# KC_BaseBoard4CompareTest-V0_1_NT.net
KiCad netlist of a schematic drawn in Altium Designer
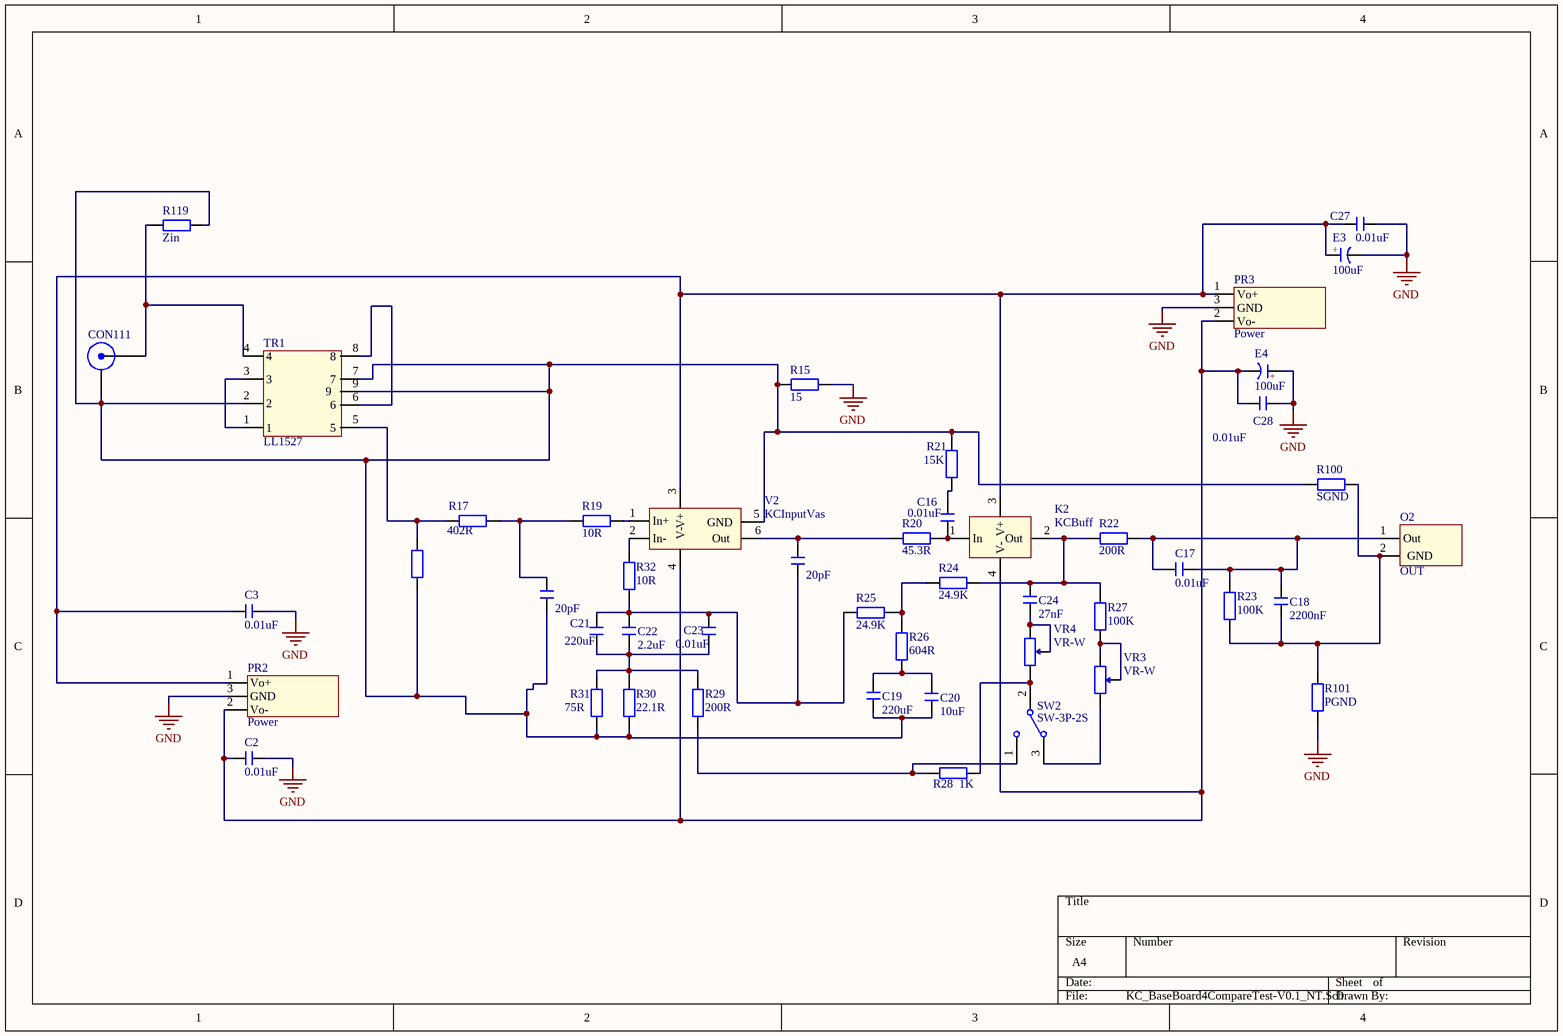
[diagram p0: KC_BaseBoard4CompareTest-V0.1_NT.SchDoc]

(export (version "E")
  (design (tool "Eeschema 10.0.6"))
  (components
    (comp (ref "C2")
      (value "0.01uF")
      (footprint "CBB 6.3*6.3*5")
      (description "CBB电容")
      (fields (field (name "版权归属") "源创客"))
      (libsource (lib "电阻-电容-电感") (part "C-CBB"))
    )
    (comp (ref "C3")
      (value "0.01uF")
      (footprint "CBB 6.3*6.3*5")
      (description "CBB电容")
      (fields (field (name "版权归属") "源创客"))
      (libsource (lib "电阻-电容-电感") (part "C-CBB"))
    )
    (comp (ref "C16")
      (value "0.01uF")
      (footprint "CBB 6.3*6.3*5")
      (description "CBB电容")
      (fields (field (name "版权归属") "源创客"))
      (libsource (lib "电阻-电容-电感") (part "C-CBB"))
    )
    (comp (ref "C17")
      (value "0.01uF")
      (footprint "CBB 6.3*6.3*5")
      (description "CBB电容")
      (fields (field (name "版权归属") "源创客"))
      (libsource (lib "电阻-电容-电感") (part "C-CBB"))
    )
    (comp (ref "C18")
      (value "2200nF")
      (footprint "CBB 6.3*6.3*5")
      (description "CBB电容")
      (fields (field (name "版权归属") "源创客"))
      (libsource (lib "电阻-电容-电感") (part "C-CBB"))
    )
    (comp (ref "C19")
      (value "220uF")
      (footprint "CBB 6.3*6.3*5")
      (description "CBB电容")
      (fields (field (name "版权归属") "源创客"))
      (libsource (lib "电阻-电容-电感") (part "C-CBB"))
    )
    (comp (ref "C20")
      (value "10uF")
      (footprint "CBB 6.3*6.3*5")
      (description "CBB电容")
      (fields (field (name "版权归属") "源创客"))
      (libsource (lib "电阻-电容-电感") (part "C-CBB"))
    )
    (comp (ref "C21")
      (value "220uF")
      (footprint "CBB 6.3*6.3*5")
      (description "CBB电容")
      (fields (field (name "版权归属") "源创客"))
      (libsource (lib "电阻-电容-电感") (part "C-CBB"))
    )
    (comp (ref "C22")
      (value "2.2uF")
      (footprint "CBB 6.3*6.3*5")
      (description "CBB电容")
      (fields (field (name "版权归属") "源创客"))
      (libsource (lib "电阻-电容-电感") (part "C-CBB"))
    )
    (comp (ref "C23")
      (value "0.01uF")
      (footprint "CBB 6.3*6.3*5")
      (description "CBB电容")
      (fields (field (name "版权归属") "源创客"))
      (libsource (lib "电阻-电容-电感") (part "C-CBB"))
    )
    (comp (ref "C24")
      (value "27nF")
      (footprint "CBB 6.3*6.3*5")
      (description "CBB电容")
      (fields (field (name "版权归属") "源创客"))
      (libsource (lib "电阻-电容-电感") (part "C-CBB"))
    )
    (comp (ref "C27")
      (value "0.01uF")
      (footprint "CBB 6.3*6.3*5")
      (description "CBB电容")
      (fields (field (name "版权归属") "源创客"))
      (libsource (lib "电阻-电容-电感") (part "C-CBB"))
    )
    (comp (ref "C28")
      (value "0.01uF")
      (footprint "CBB 6.3*6.3*5")
      (description "CBB电容")
      (fields (field (name "版权归属") "源创客"))
      (libsource (lib "电阻-电容-电感") (part "C-CBB"))
    )
    (comp (ref "C303")
      (value "20pF")
      (footprint "CBB 6.3*6.3*5")
      (description "CBB电容")
      (fields (field (name "版权归属") "源创客"))
      (libsource (lib "电阻-电容-电感") (part "C-CBB"))
    )
    (comp (ref "C403")
      (value "20pF")
      (footprint "CBB 6.3*6.3*5")
      (description "CBB电容")
      (fields (field (name "版权归属") "源创客"))
      (libsource (lib "电阻-电容-电感") (part "C-CBB"))
    )
    (comp (ref "CON111")
      (value "RCA")
      (footprint "SMB_V-RJ45")
      (description "RCA Connector")
      (fields (field (name "PUBLISHER") "Altium Limited"))
      (libsource (lib "Connectors") (part "RCA"))
    )
    (comp (ref "E3")
      (value "100uF")
      (footprint "CAP 5.0*6.5*12.5")
      (description "直插电解电容")
      (fields (field (name "版权归属") "源创客"))
      (libsource (lib "电阻-电容-电感") (part "C-CAP"))
    )
    (comp (ref "E4")
      (value "100uF")
      (footprint "CAP 5.0*6.5*12.5")
      (description "直插电解电容")
      (fields (field (name "版权归属") "源创客"))
      (libsource (lib "电阻-电容-电感") (part "C-CAP"))
    )
    (comp (ref "K2")
      (value "KCBuff")
      (footprint "KCBuff_M4")
      (description "King Cello Buffer Stage")
      (libsource (lib "KC_amp") (part "KCBuff"))
    )
    (comp (ref "O2")
      (value "OUT")
      (footprint "Signal_Terminal")
      (description "Signal Out")
      (libsource (lib "KC_amp") (part "Signal_Out"))
    )
    (comp (ref "PR2")
      (value "Power")
      (footprint "KC_MBPowerReg4Compare-1.5mm")
      (description "King Cello Compare Test Power")
      (libsource (lib "KC_amp") (part "MainBoardPowerRegulator4CompareTest"))
    )
    (comp (ref "PR3")
      (value "Power")
      (footprint "KC_MBPowerReg4Compare-1.5mm")
      (description "King Cello Compare Test Power")
      (libsource (lib "KC_amp") (part "MainBoardPowerRegulator4CompareTest"))
    )
    (comp (ref "R15")
      (value "15")
      (footprint "RS 1/4W")
      (description "直插色环电阻")
      (fields (field (name "版权归属") "源创客"))
      (libsource (lib "电阻-电容-电感") (part "R-CRR"))
    )
    (comp (ref "R17")
      (value "402R")
      (footprint "RS 1/4W")
      (description "直插色环电阻")
      (fields (field (name "版权归属") "源创客"))
      (libsource (lib "电阻-电容-电感") (part "R-CRR"))
    )
    (comp (ref "R19")
      (value "10R")
      (footprint "RS 1/4W")
      (description "直插色环电阻")
      (fields (field (name "版权归属") "源创客"))
      (libsource (lib "电阻-电容-电感") (part "R-CRR"))
    )
    (comp (ref "R20")
      (value "45.3R")
      (footprint "RS 1/4W")
      (description "直插色环电阻")
      (fields (field (name "版权归属") "源创客"))
      (libsource (lib "电阻-电容-电感") (part "R-CRR"))
    )
    (comp (ref "R21")
      (value "15K")
      (footprint "RS 1/4W")
      (description "直插色环电阻")
      (fields (field (name "版权归属") "源创客"))
      (libsource (lib "电阻-电容-电感") (part "R-CRR"))
    )
    (comp (ref "R22")
      (value "200R")
      (footprint "RS 1/4W")
      (description "直插色环电阻")
      (fields (field (name "版权归属") "源创客"))
      (libsource (lib "电阻-电容-电感") (part "R-CRR"))
    )
    (comp (ref "R23")
      (value "100K")
      (footprint "RS 1/4W")
      (description "直插色环电阻")
      (fields (field (name "版权归属") "源创客"))
      (libsource (lib "电阻-电容-电感") (part "R-CRR"))
    )
    (comp (ref "R24")
      (value "24.9K")
      (footprint "RS 1/4W")
      (description "直插色环电阻")
      (fields (field (name "版权归属") "源创客"))
      (libsource (lib "电阻-电容-电感") (part "R-CRR"))
    )
    (comp (ref "R25")
      (value "24.9K")
      (footprint "RS 1/4W")
      (description "直插色环电阻")
      (fields (field (name "版权归属") "源创客"))
      (libsource (lib "电阻-电容-电感") (part "R-CRR"))
    )
    (comp (ref "R26")
      (value "604R")
      (footprint "RS 1/4W")
      (description "直插色环电阻")
      (fields (field (name "版权归属") "源创客"))
      (libsource (lib "电阻-电容-电感") (part "R-CRR"))
    )
    (comp (ref "R27")
      (value "100K")
      (footprint "RS 1/4W")
      (description "直插色环电阻")
      (fields (field (name "版权归属") "源创客"))
      (libsource (lib "电阻-电容-电感") (part "R-CRR"))
    )
    (comp (ref "R28")
      (value "1K")
      (footprint "RS 1/4W")
      (description "直插色环电阻")
      (fields (field (name "版权归属") "源创客"))
      (libsource (lib "电阻-电容-电感") (part "R-CRR"))
    )
    (comp (ref "R29")
      (value "200R")
      (footprint "RS 1/4W")
      (description "直插色环电阻")
      (fields (field (name "版权归属") "源创客"))
      (libsource (lib "电阻-电容-电感") (part "R-CRR"))
    )
    (comp (ref "R30")
      (value "22.1R")
      (footprint "RS 1/4W")
      (description "直插色环电阻")
      (fields (field (name "版权归属") "源创客"))
      (libsource (lib "电阻-电容-电感") (part "R-CRR"))
    )
    (comp (ref "R31")
      (value "75R")
      (footprint "RS 1/4W")
      (description "直插色环电阻")
      (fields (field (name "版权归属") "源创客"))
      (libsource (lib "电阻-电容-电感") (part "R-CRR"))
    )
    (comp (ref "R32")
      (value "10R")
      (footprint "RS 1/4W")
      (description "直插色环电阻")
      (fields (field (name "版权归属") "源创客"))
      (libsource (lib "电阻-电容-电感") (part "R-CRR"))
    )
    (comp (ref "R100")
      (value "SGND")
      (footprint "RS 1/4W")
      (description "直插色环电阻")
      (fields (field (name "版权归属") "源创客"))
      (libsource (lib "电阻-电容-电感") (part "R-CRR"))
    )
    (comp (ref "R101")
      (value "PGND")
      (footprint "RS 1/4W")
      (description "直插色环电阻")
      (fields (field (name "版权归属") "源创客"))
      (libsource (lib "电阻-电容-电感") (part "R-CRR"))
    )
    (comp (ref "R119")
      (value "Zin")
      (footprint "RS 1/4W")
      (description "直插色环电阻")
      (fields (field (name "版权归属") "源创客"))
      (libsource (lib "电阻-电容-电感") (part "R-CRR"))
    )
    (comp (ref "R183")
      (value "47K")
      (footprint "RS 1/4W")
      (description "直插色环电阻")
      (fields (field (name "版权归属") "源创客"))
      (libsource (lib "电阻-电容-电感") (part "R-CRR"))
    )
    (comp (ref "SW2")
      (value "SW-3P-2S")
      (footprint "SS-12D06")
      (description "3 Pin 2 Switch")
      (libsource (lib "Connectors") (part "SW-3P-2S"))
    )
    (comp (ref "TR1")
      (value "LL1527")
      (footprint "LL1527")
      (description "Lundahl LL1527")
      (libsource (lib "KC_amp") (part "LL1527"))
    )
    (comp (ref "V2")
      (value "KCInputVas")
      (footprint "KCIn_VAS_M4")
      (description "King Cello Input Stage and VAS")
      (libsource (lib "KC_amp") (part "KCInputVas"))
    )
    (comp (ref "VR3")
      (value "VR-W")
      (footprint "RS 1/2W-VR")
      (description "直插可调电阻-顶调")
      (libsource (lib "电阻-电容-电感") (part "VR-W"))
    )
    (comp (ref "VR4")
      (value "VR-W")
      (footprint "RS 1/2W-VR")
      (description "直插可调电阻-顶调")
      (libsource (lib "电阻-电容-电感") (part "VR-W"))
    )
  )
  (nets
    (net (code "1") (name "GND") (class "Default")
      (node (ref "C2") (pin "2") (pinfunction "2_2") (pintype "passive"))
      (node (ref "C27") (pin "2") (pinfunction "2_2") (pintype "passive"))
      (node (ref "C28") (pin "2") (pinfunction "2_2") (pintype "passive"))
      (node (ref "C3") (pin "2") (pinfunction "2_2") (pintype "passive"))
      (node (ref "E3") (pin "2") (pinfunction "K_2") (pintype "passive"))
      (node (ref "E4") (pin "1") (pinfunction "A_1") (pintype "passive"))
      (node (ref "PR2") (pin "3") (pinfunction "GND_3") (pintype "passive"))
      (node (ref "PR3") (pin "3") (pinfunction "GND_3") (pintype "passive"))
      (node (ref "R101") (pin "1") (pinfunction "1_1") (pintype "passive"))
      (node (ref "R15") (pin "2") (pinfunction "2_2") (pintype "passive"))
    )
    (net (code "2") (name "Net-(C16-Pad2)") (class "Default")
      (node (ref "C16") (pin "2") (pinfunction "2_2") (pintype "passive"))
      (node (ref "R21") (pin "1") (pinfunction "1_1") (pintype "passive"))
    )
    (net (code "3") (name "Net-(C19-Pad1)") (class "Default")
      (node (ref "C19") (pin "1") (pinfunction "1_1") (pintype "passive"))
      (node (ref "C20") (pin "1") (pinfunction "1_1") (pintype "passive"))
      (node (ref "R26") (pin "1") (pinfunction "1_1") (pintype "passive"))
    )
    (net (code "4") (name "Net-(C21-Pad1)") (class "Default")
      (node (ref "C21") (pin "1") (pinfunction "1_1") (pintype "passive"))
      (node (ref "C22") (pin "1") (pinfunction "1_1") (pintype "passive"))
      (node (ref "C23") (pin "1") (pinfunction "1_1") (pintype "passive"))
      (node (ref "C403") (pin "1") (pinfunction "1_1") (pintype "passive"))
      (node (ref "R25") (pin "1") (pinfunction "1_1") (pintype "passive"))
      (node (ref "R32") (pin "1") (pinfunction "1_1") (pintype "passive"))
    )
    (net (code "5") (name "Net-(C21-Pad2)") (class "Default")
      (node (ref "C21") (pin "2") (pinfunction "2_2") (pintype "passive"))
      (node (ref "C22") (pin "2") (pinfunction "2_2") (pintype "passive"))
      (node (ref "C23") (pin "2") (pinfunction "2_2") (pintype "passive"))
      (node (ref "R29") (pin "2") (pinfunction "2_2") (pintype "passive"))
      (node (ref "R30") (pin "2") (pinfunction "2_2") (pintype "passive"))
      (node (ref "R31") (pin "2") (pinfunction "2_2") (pintype "passive"))
    )
    (net (code "6") (name "Net-(C24-Pad2)") (class "Default")
      (node (ref "C24") (pin "2") (pinfunction "2_2") (pintype "passive"))
      (node (ref "VR4") (pin "1") (pinfunction "1_1") (pintype "passive"))
      (node (ref "VR4") (pin "3") (pinfunction "3_3") (pintype "passive"))
    )
    (net (code "7") (name "Net-(C303-Pad2)") (class "Default")
      (node (ref "C303") (pin "2") (pinfunction "2_2") (pintype "passive"))
      (node (ref "R17") (pin "2") (pinfunction "2_2") (pintype "passive"))
      (node (ref "R19") (pin "1") (pinfunction "1_1") (pintype "passive"))
    )
    (net (code "8") (name "Net-(CON111-X)") (class "Default")
      (node (ref "CON111") (pin "1") (pinfunction "X_1") (pintype "passive"))
      (node (ref "R119") (pin "1") (pinfunction "1_1") (pintype "passive"))
      (node (ref "TR1") (pin "4") (pinfunction "4_4") (pintype "passive"))
    )
    (net (code "9") (name "Net-(CON111-Y)") (class "Default")
      (node (ref "C19") (pin "2") (pinfunction "2_2") (pintype "passive"))
      (node (ref "C20") (pin "2") (pinfunction "2_2") (pintype "passive"))
      (node (ref "C303") (pin "1") (pinfunction "1_1") (pintype "passive"))
      (node (ref "CON111") (pin "2") (pinfunction "Y_2") (pintype "passive"))
      (node (ref "R100") (pin "1") (pinfunction "1_1") (pintype "passive"))
      (node (ref "R119") (pin "2") (pinfunction "2_2") (pintype "passive"))
      (node (ref "R15") (pin "1") (pinfunction "1_1") (pintype "passive"))
      (node (ref "R183") (pin "1") (pinfunction "1_1") (pintype "passive"))
      (node (ref "R21") (pin "2") (pinfunction "2_2") (pintype "passive"))
      (node (ref "R30") (pin "1") (pinfunction "1_1") (pintype "passive"))
      (node (ref "R31") (pin "1") (pinfunction "1_1") (pintype "passive"))
      (node (ref "TR1") (pin "2") (pinfunction "2_2") (pintype "passive"))
      (node (ref "TR1") (pin "7") (pinfunction "7_7") (pintype "passive"))
      (node (ref "TR1") (pin "9") (pinfunction "9_9") (pintype "passive"))
      (node (ref "V2") (pin "5") (pinfunction "GND_5") (pintype "passive"))
    )
    (net (code "10") (name "Net-(E3-A)") (class "Default")
      (node (ref "C27") (pin "1") (pinfunction "1_1") (pintype "passive"))
      (node (ref "C3") (pin "1") (pinfunction "1_1") (pintype "passive"))
      (node (ref "E3") (pin "1") (pinfunction "A_1") (pintype "passive"))
      (node (ref "K2") (pin "3") (pinfunction "V+_3") (pintype "passive"))
      (node (ref "PR2") (pin "1") (pinfunction "Vo+_1") (pintype "passive"))
      (node (ref "PR3") (pin "1") (pinfunction "Vo+_1") (pintype "passive"))
      (node (ref "V2") (pin "3") (pinfunction "V+_3") (pintype "passive"))
    )
    (net (code "11") (name "Net-(E4-K)") (class "Default")
      (node (ref "C2") (pin "1") (pinfunction "1_1") (pintype "passive"))
      (node (ref "C28") (pin "1") (pinfunction "1_1") (pintype "passive"))
      (node (ref "E4") (pin "2") (pinfunction "K_2") (pintype "passive"))
      (node (ref "K2") (pin "4") (pinfunction "V-_4") (pintype "passive"))
      (node (ref "PR2") (pin "2") (pinfunction "Vo-_2") (pintype "passive"))
      (node (ref "PR3") (pin "2") (pinfunction "Vo-_2") (pintype "passive"))
      (node (ref "V2") (pin "4") (pinfunction "V-_4") (pintype "passive"))
    )
    (net (code "12") (name "Net-(K2-In)") (class "Default")
      (node (ref "C16") (pin "1") (pinfunction "1_1") (pintype "passive"))
      (node (ref "K2") (pin "1") (pinfunction "In_1") (pintype "passive"))
      (node (ref "R20") (pin "2") (pinfunction "2_2") (pintype "passive"))
    )
    (net (code "13") (name "Net-(K2-Out)") (class "Default")
      (node (ref "C24") (pin "1") (pinfunction "1_1") (pintype "passive"))
      (node (ref "K2") (pin "2") (pinfunction "Out_2") (pintype "passive"))
      (node (ref "R22") (pin "2") (pinfunction "2_2") (pintype "passive"))
      (node (ref "R24") (pin "2") (pinfunction "2_2") (pintype "passive"))
      (node (ref "R27") (pin "1") (pinfunction "1_1") (pintype "passive"))
    )
    (net (code "14") (name "Net-(O2-GND)") (class "Default")
      (node (ref "C18") (pin "2") (pinfunction "2_2") (pintype "passive"))
      (node (ref "O2") (pin "2") (pinfunction "GND_2") (pintype "passive"))
      (node (ref "R100") (pin "2") (pinfunction "2_2") (pintype "passive"))
      (node (ref "R101") (pin "2") (pinfunction "2_2") (pintype "passive"))
      (node (ref "R23") (pin "2") (pinfunction "2_2") (pintype "passive"))
    )
    (net (code "15") (name "Net-(O2-Out)") (class "Default")
      (node (ref "C17") (pin "1") (pinfunction "1_1") (pintype "passive"))
      (node (ref "C17") (pin "2") (pinfunction "2_2") (pintype "passive"))
      (node (ref "C18") (pin "1") (pinfunction "1_1") (pintype "passive"))
      (node (ref "O2") (pin "1") (pinfunction "Out_1") (pintype "passive"))
      (node (ref "R22") (pin "1") (pinfunction "1_1") (pintype "passive"))
      (node (ref "R23") (pin "1") (pinfunction "1_1") (pintype "passive"))
    )
    (net (code "16") (name "Net-(R17-Pad1)") (class "Default")
      (node (ref "R17") (pin "1") (pinfunction "1_1") (pintype "passive"))
      (node (ref "R183") (pin "2") (pinfunction "2_2") (pintype "passive"))
      (node (ref "TR1") (pin "5") (pinfunction "5_5") (pintype "passive"))
    )
    (net (code "17") (name "Net-(R24-Pad1)") (class "Default")
      (node (ref "R24") (pin "1") (pinfunction "1_1") (pintype "passive"))
      (node (ref "R25") (pin "2") (pinfunction "2_2") (pintype "passive"))
      (node (ref "R26") (pin "2") (pinfunction "2_2") (pintype "passive"))
    )
    (net (code "18") (name "Net-(R27-Pad2)") (class "Default")
      (node (ref "R27") (pin "2") (pinfunction "2_2") (pintype "passive"))
      (node (ref "VR3") (pin "1") (pinfunction "1_1") (pintype "passive"))
      (node (ref "VR3") (pin "3") (pinfunction "3_3") (pintype "passive"))
    )
    (net (code "19") (name "Net-(R28-Pad1)") (class "Default")
      (node (ref "R28") (pin "1") (pinfunction "1_1") (pintype "passive"))
      (node (ref "R29") (pin "1") (pinfunction "1_1") (pintype "passive"))
      (node (ref "SW2") (pin "1") (pinfunction "1_1") (pintype "passive"))
    )
    (net (code "20") (name "Net-(R28-Pad2)") (class "Default")
      (node (ref "R28") (pin "2") (pinfunction "2_2") (pintype "passive"))
      (node (ref "SW2") (pin "2") (pinfunction "2_2") (pintype "passive"))
      (node (ref "VR4") (pin "2") (pinfunction "2_2") (pintype "passive"))
    )
    (net (code "21") (name "Net-(SW2-Pad3)") (class "Default")
      (node (ref "SW2") (pin "3") (pinfunction "3_3") (pintype "passive"))
      (node (ref "VR3") (pin "2") (pinfunction "2_2") (pintype "passive"))
    )
    (net (code "22") (name "Net-(TR1-Pad1)") (class "Default")
      (node (ref "TR1") (pin "1") (pinfunction "1_1") (pintype "passive"))
      (node (ref "TR1") (pin "3") (pinfunction "3_3") (pintype "passive"))
    )
    (net (code "23") (name "Net-(TR1-Pad6)") (class "Default")
      (node (ref "TR1") (pin "6") (pinfunction "6_6") (pintype "passive"))
      (node (ref "TR1") (pin "8") (pinfunction "8_8") (pintype "passive"))
    )
    (net (code "24") (name "Net-(V2-In+)") (class "Default")
      (node (ref "R19") (pin "2") (pinfunction "2_2") (pintype "passive"))
      (node (ref "V2") (pin "1") (pinfunction "In+_1") (pintype "passive"))
    )
    (net (code "25") (name "Net-(V2-In-)") (class "Default")
      (node (ref "R32") (pin "2") (pinfunction "2_2") (pintype "passive"))
      (node (ref "V2") (pin "2") (pinfunction "In-_2") (pintype "passive"))
    )
    (net (code "26") (name "Net-(V2-Out)") (class "Default")
      (node (ref "C403") (pin "2") (pinfunction "2_2") (pintype "passive"))
      (node (ref "R20") (pin "1") (pinfunction "1_1") (pintype "passive"))
      (node (ref "V2") (pin "6") (pinfunction "Out_6") (pintype "passive"))
    )
  )
)
